# H3_MIDIController_Rev_2_MainBoard.net
KiCad netlist of a schematic drawn in EAGLE
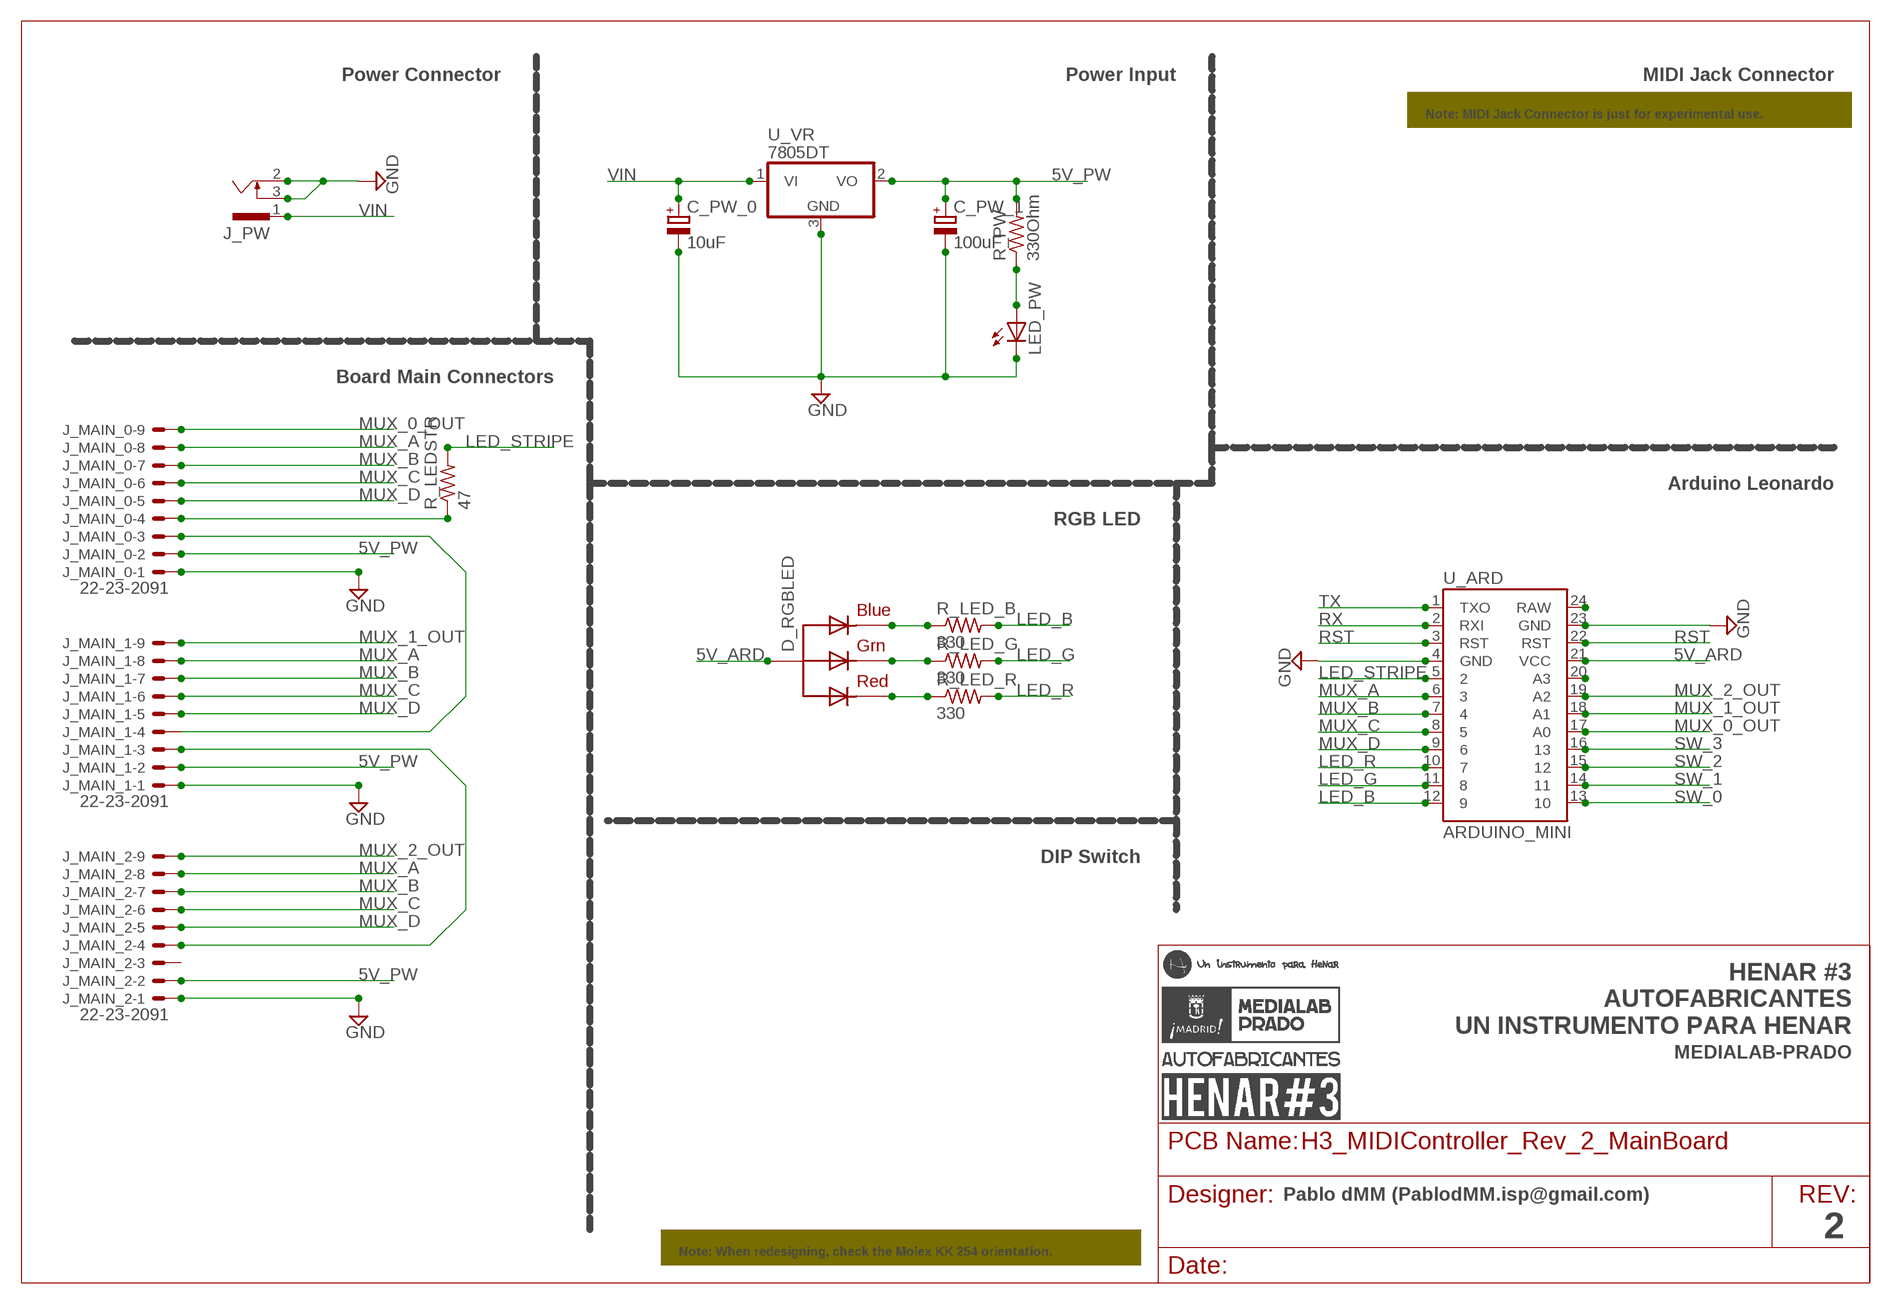
[diagram p0: schematic, sheet 1]

(export (version "E")
  (design (tool "Eeschema 10.0.6"))
  (components
    (comp (ref "C_PW_0")
      (value "10uF")
      (footprint "eagle-import:TT2D6L")
      (libsource (lib "eagle-import") (part "CPOL-EUTT2D6L"))
    )
    (comp (ref "C_PW_1")
      (value "100uF")
      (footprint "eagle-import:TT2D6L")
      (libsource (lib "eagle-import") (part "CPOL-EUTT2D6L"))
    )
    (comp (ref "D_RGBLED")
      (value "RGBLED_CA-5MM")
      (footprint "eagle-import:LED5MMRGB")
      (libsource (lib "eagle-import") (part "RGBLED_CA-5MM"))
    )
    (comp (ref "J_MAIN_0")
      (value "22-23-2091")
      (footprint "eagle-import:22-23-2091")
      (fields (field (name "MF") "MOLEX"))
      (libsource (lib "eagle-import") (part "22-23-2091"))
    )
    (comp (ref "J_MAIN_1")
      (value "22-23-2091")
      (footprint "eagle-import:22-23-2091")
      (fields (field (name "MF") "MOLEX"))
      (libsource (lib "eagle-import") (part "22-23-2091"))
    )
    (comp (ref "J_MAIN_2")
      (value "22-23-2091")
      (footprint "eagle-import:22-23-2091")
      (fields (field (name "MF") "MOLEX"))
      (libsource (lib "eagle-import") (part "22-23-2091"))
    )
    (comp (ref "J_PW")
      (value "SCD-014A")
      (footprint "eagle-import:SCD-014-A")
      (libsource (lib "eagle-import") (part "SCD-014A"))
    )
    (comp (ref "LED_PW")
      (value "LEDSMT1206")
      (footprint "eagle-import:1206")
      (libsource (lib "eagle-import") (part "LEDSMT1206"))
    )
    (comp (ref "R_LEDSTR")
      (value "47")
      (footprint "eagle-import:M1206")
      (libsource (lib "eagle-import") (part "R-US_M1206"))
    )
    (comp (ref "R_LED_B")
      (value "330")
      (footprint "eagle-import:M1206")
      (libsource (lib "eagle-import") (part "R-US_M1206"))
    )
    (comp (ref "R_LED_G")
      (value "330")
      (footprint "eagle-import:M1206")
      (libsource (lib "eagle-import") (part "R-US_M1206"))
    )
    (comp (ref "R_LED_R")
      (value "330")
      (footprint "eagle-import:M1206")
      (libsource (lib "eagle-import") (part "R-US_M1206"))
    )
    (comp (ref "R_PW")
      (value "330Ohm")
      (footprint "eagle-import:M1206")
      (libsource (lib "eagle-import") (part "R-US_M1206"))
    )
    (comp (ref "U_ARD")
      (value "ARDUINO_MINI")
      (footprint "eagle-import:ARDUINO_MINI")
      (libsource (lib "eagle-import") (part "ARDUINO_MINI"))
    )
    (comp (ref "U_VR")
      (value "7805DT")
      (footprint "eagle-import:TO252")
      (libsource (lib "eagle-import") (part "78DT05"))
    )
  )
  (nets
    (net (code "1") (name "/5V_ARD") (class "Default")
      (node (ref "D_RGBLED") (pin "2") (pinfunction "VCC_2") (pintype "bidirectional"))
      (node (ref "U_ARD") (pin "21") (pinfunction "VCC_21") (pintype "bidirectional"))
    )
    (net (code "2") (name "/5V_PW") (class "Default")
      (node (ref "C_PW_1") (pin "+") (pinfunction "+_+") (pintype "passive"))
      (node (ref "J_MAIN_0") (pin "2") (pinfunction "S_2") (pintype "passive"))
      (node (ref "J_MAIN_1") (pin "2") (pinfunction "S_2") (pintype "passive"))
      (node (ref "J_MAIN_2") (pin "2") (pinfunction "S_2") (pintype "passive"))
      (node (ref "R_PW") (pin "2") (pinfunction "2_2") (pintype "passive"))
      (node (ref "U_VR") (pin "2") (pinfunction "VO_2") (pintype "passive"))
    )
    (net (code "3") (name "/LED_B") (class "Default")
      (node (ref "R_LED_B") (pin "2") (pinfunction "2_2") (pintype "passive"))
      (node (ref "U_ARD") (pin "12") (pinfunction "9_12") (pintype "bidirectional"))
    )
    (net (code "4") (name "/LED_G") (class "Default")
      (node (ref "R_LED_G") (pin "2") (pinfunction "2_2") (pintype "passive"))
      (node (ref "U_ARD") (pin "11") (pinfunction "8_11") (pintype "bidirectional"))
    )
    (net (code "5") (name "/LED_R") (class "Default")
      (node (ref "R_LED_R") (pin "2") (pinfunction "2_2") (pintype "passive"))
      (node (ref "U_ARD") (pin "10") (pinfunction "7_10") (pintype "bidirectional"))
    )
    (net (code "6") (name "/LED_STRIPE") (class "Default")
      (node (ref "R_LEDSTR") (pin "2") (pinfunction "2_2") (pintype "passive"))
      (node (ref "U_ARD") (pin "5") (pinfunction "2_5") (pintype "bidirectional"))
    )
    (net (code "7") (name "/MUX_0_OUT") (class "Default")
      (node (ref "J_MAIN_0") (pin "9") (pinfunction "S_9") (pintype "passive"))
      (node (ref "U_ARD") (pin "17") (pinfunction "A0_17") (pintype "bidirectional"))
    )
    (net (code "8") (name "/MUX_1_OUT") (class "Default")
      (node (ref "J_MAIN_1") (pin "9") (pinfunction "S_9") (pintype "passive"))
      (node (ref "U_ARD") (pin "18") (pinfunction "A1_18") (pintype "bidirectional"))
    )
    (net (code "9") (name "/MUX_2_OUT") (class "Default")
      (node (ref "J_MAIN_2") (pin "9") (pinfunction "S_9") (pintype "passive"))
      (node (ref "U_ARD") (pin "19") (pinfunction "A2_19") (pintype "bidirectional"))
    )
    (net (code "10") (name "/MUX_A") (class "Default")
      (node (ref "J_MAIN_0") (pin "8") (pinfunction "S_8") (pintype "passive"))
      (node (ref "J_MAIN_1") (pin "8") (pinfunction "S_8") (pintype "passive"))
      (node (ref "J_MAIN_2") (pin "8") (pinfunction "S_8") (pintype "passive"))
      (node (ref "U_ARD") (pin "6") (pinfunction "3_6") (pintype "bidirectional"))
    )
    (net (code "11") (name "/MUX_B") (class "Default")
      (node (ref "J_MAIN_0") (pin "7") (pinfunction "S_7") (pintype "passive"))
      (node (ref "J_MAIN_1") (pin "7") (pinfunction "S_7") (pintype "passive"))
      (node (ref "J_MAIN_2") (pin "7") (pinfunction "S_7") (pintype "passive"))
      (node (ref "U_ARD") (pin "7") (pinfunction "4_7") (pintype "bidirectional"))
    )
    (net (code "12") (name "/MUX_C") (class "Default")
      (node (ref "J_MAIN_0") (pin "6") (pinfunction "S_6") (pintype "passive"))
      (node (ref "J_MAIN_1") (pin "6") (pinfunction "S_6") (pintype "passive"))
      (node (ref "J_MAIN_2") (pin "6") (pinfunction "S_6") (pintype "passive"))
      (node (ref "U_ARD") (pin "8") (pinfunction "5_8") (pintype "bidirectional"))
    )
    (net (code "13") (name "/MUX_D") (class "Default")
      (node (ref "J_MAIN_0") (pin "5") (pinfunction "S_5") (pintype "passive"))
      (node (ref "J_MAIN_1") (pin "5") (pinfunction "S_5") (pintype "passive"))
      (node (ref "J_MAIN_2") (pin "5") (pinfunction "S_5") (pintype "passive"))
      (node (ref "U_ARD") (pin "9") (pinfunction "6_9") (pintype "bidirectional"))
    )
    (net (code "14") (name "/RST") (class "Default")
      (node (ref "U_ARD") (pin "22") (pinfunction "RST_22") (pintype "bidirectional"))
      (node (ref "U_ARD") (pin "3") (pinfunction "RST_3") (pintype "bidirectional"))
    )
    (net (code "15") (name "/RX") (class "Default")
      (node (ref "U_ARD") (pin "2") (pinfunction "RXI_2") (pintype "bidirectional"))
    )
    (net (code "16") (name "/SW_0") (class "Default")
      (node (ref "U_ARD") (pin "13") (pinfunction "10_13") (pintype "bidirectional"))
    )
    (net (code "17") (name "/SW_1") (class "Default")
      (node (ref "U_ARD") (pin "14") (pinfunction "11_14") (pintype "bidirectional"))
    )
    (net (code "18") (name "/SW_2") (class "Default")
      (node (ref "U_ARD") (pin "15") (pinfunction "12_15") (pintype "bidirectional"))
    )
    (net (code "19") (name "/SW_3") (class "Default")
      (node (ref "U_ARD") (pin "16") (pinfunction "13_16") (pintype "bidirectional"))
    )
    (net (code "20") (name "/TX") (class "Default")
      (node (ref "U_ARD") (pin "1") (pinfunction "TXO_1") (pintype "bidirectional"))
    )
    (net (code "21") (name "/VIN") (class "Default")
      (node (ref "C_PW_0") (pin "+") (pinfunction "+_+") (pintype "passive"))
      (node (ref "J_PW") (pin "1") (pinfunction "1_1") (pintype "passive"))
      (node (ref "U_VR") (pin "1") (pinfunction "VI_1") (pintype "input"))
    )
    (net (code "22") (name "GND") (class "Default")
      (node (ref "C_PW_0") (pin "-") (pinfunction "-_-") (pintype "passive"))
      (node (ref "C_PW_1") (pin "-") (pinfunction "-_-") (pintype "passive"))
      (node (ref "J_MAIN_0") (pin "1") (pinfunction "S_1") (pintype "passive"))
      (node (ref "J_MAIN_1") (pin "1") (pinfunction "S_1") (pintype "passive"))
      (node (ref "J_MAIN_2") (pin "1") (pinfunction "S_1") (pintype "passive"))
      (node (ref "J_PW") (pin "2") (pinfunction "2_2") (pintype "passive"))
      (node (ref "J_PW") (pin "3") (pinfunction "3_3") (pintype "passive"))
      (node (ref "LED_PW") (pin "C") (pinfunction "C_C") (pintype "passive"))
      (node (ref "U_ARD") (pin "23") (pinfunction "GND_23") (pintype "bidirectional"))
      (node (ref "U_ARD") (pin "4") (pinfunction "GND_4") (pintype "bidirectional"))
      (node (ref "U_VR") (pin "3") (pinfunction "GND_3") (pintype "passive"))
    )
    (net (code "23") (name "Net-(D_RGBLED-BLUE)") (class "Default")
      (node (ref "D_RGBLED") (pin "4") (pinfunction "BLUE_4") (pintype "bidirectional"))
      (node (ref "R_LED_B") (pin "1") (pinfunction "1_1") (pintype "passive"))
    )
    (net (code "24") (name "Net-(D_RGBLED-GREEN)") (class "Default")
      (node (ref "D_RGBLED") (pin "3") (pinfunction "GREEN_3") (pintype "bidirectional"))
      (node (ref "R_LED_G") (pin "1") (pinfunction "1_1") (pintype "passive"))
    )
    (net (code "25") (name "Net-(D_RGBLED-RED)") (class "Default")
      (node (ref "D_RGBLED") (pin "1") (pinfunction "RED_1") (pintype "bidirectional"))
      (node (ref "R_LED_R") (pin "1") (pinfunction "1_1") (pintype "passive"))
    )
    (net (code "26") (name "Net-(J_MAIN_0C-S)") (class "Default")
      (node (ref "J_MAIN_0") (pin "3") (pinfunction "S_3") (pintype "passive"))
      (node (ref "J_MAIN_1") (pin "4") (pinfunction "S_4") (pintype "passive"))
    )
    (net (code "27") (name "Net-(J_MAIN_0D-S)") (class "Default")
      (node (ref "J_MAIN_0") (pin "4") (pinfunction "S_4") (pintype "passive"))
      (node (ref "R_LEDSTR") (pin "1") (pinfunction "1_1") (pintype "passive"))
    )
    (net (code "28") (name "Net-(J_MAIN_1C-S)") (class "Default")
      (node (ref "J_MAIN_1") (pin "3") (pinfunction "S_3") (pintype "passive"))
      (node (ref "J_MAIN_2") (pin "4") (pinfunction "S_4") (pintype "passive"))
    )
    (net (code "29") (name "Net-(LED_PW-PadA)") (class "Default")
      (node (ref "LED_PW") (pin "A") (pinfunction "A_A") (pintype "passive"))
      (node (ref "R_PW") (pin "1") (pinfunction "1_1") (pintype "passive"))
    )
    (net (code "30") (name "unconnected-(J_MAIN_2C-S-Pad3)") (class "Default")
      (node (ref "J_MAIN_2") (pin "3") (pinfunction "S_3") (pintype "passive"))
    )
    (net (code "31") (name "unconnected-(U_ARD-A3-Pad20)") (class "Default")
      (node (ref "U_ARD") (pin "20") (pinfunction "A3_20") (pintype "bidirectional"))
    )
    (net (code "32") (name "unconnected-(U_ARD-RAW-Pad24)") (class "Default")
      (node (ref "U_ARD") (pin "24") (pinfunction "RAW_24") (pintype "bidirectional"))
    )
  )
)
